# NTC_6_Shoulder.net
KiCad netlist of a schematic drawn in Altium Designer
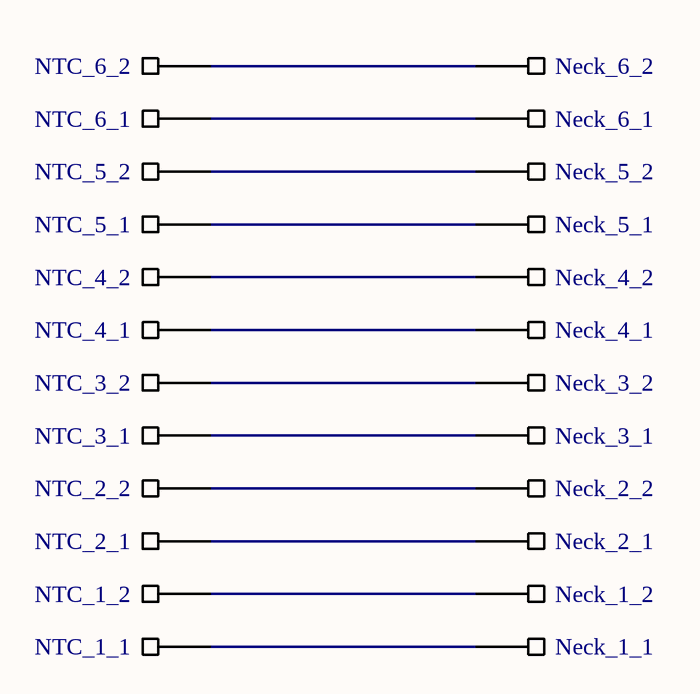
[diagram p0: NTC_6_Shoulder.SchDoc]

(export (version "E")
  (design (tool "Eeschema 10.0.6"))
  (components
    (comp (ref "Neck_1_1")
      (value "Pad")
      (footprint "Generic_Pad_1.5x1.5")
      (description "Pad 1.5mm x 1.5mm")
      (libsource (lib "libNico") (part "Generic_Pad_1.5x1.5"))
    )
    (comp (ref "Neck_1_2")
      (value "Pad")
      (footprint "Generic_Pad_1.5x1.5")
      (description "Pad 1.5mm x 1.5mm")
      (libsource (lib "libNico") (part "Generic_Pad_1.5x1.5"))
    )
    (comp (ref "Neck_2_1")
      (value "Pad")
      (footprint "Generic_Pad_1.5x1.5")
      (description "Pad 1.5mm x 1.5mm")
      (libsource (lib "libNico") (part "Generic_Pad_1.5x1.5"))
    )
    (comp (ref "Neck_2_2")
      (value "Pad")
      (footprint "Generic_Pad_1.5x1.5")
      (description "Pad 1.5mm x 1.5mm")
      (libsource (lib "libNico") (part "Generic_Pad_1.5x1.5"))
    )
    (comp (ref "Neck_3_1")
      (value "Pad")
      (footprint "Generic_Pad_1.5x1.5")
      (description "Pad 1.5mm x 1.5mm")
      (libsource (lib "libNico") (part "Generic_Pad_1.5x1.5"))
    )
    (comp (ref "Neck_3_2")
      (value "Pad")
      (footprint "Generic_Pad_1.5x1.5")
      (description "Pad 1.5mm x 1.5mm")
      (libsource (lib "libNico") (part "Generic_Pad_1.5x1.5"))
    )
    (comp (ref "Neck_4_1")
      (value "Pad")
      (footprint "Generic_Pad_1.5x1.5")
      (description "Pad 1.5mm x 1.5mm")
      (libsource (lib "libNico") (part "Generic_Pad_1.5x1.5"))
    )
    (comp (ref "Neck_4_2")
      (value "Pad")
      (footprint "Generic_Pad_1.5x1.5")
      (description "Pad 1.5mm x 1.5mm")
      (libsource (lib "libNico") (part "Generic_Pad_1.5x1.5"))
    )
    (comp (ref "Neck_5_1")
      (value "Pad")
      (footprint "Generic_Pad_1.5x1.5")
      (description "Pad 1.5mm x 1.5mm")
      (libsource (lib "libNico") (part "Generic_Pad_1.5x1.5"))
    )
    (comp (ref "Neck_5_2")
      (value "Pad")
      (footprint "Generic_Pad_1.5x1.5")
      (description "Pad 1.5mm x 1.5mm")
      (libsource (lib "libNico") (part "Generic_Pad_1.5x1.5"))
    )
    (comp (ref "Neck_6_1")
      (value "Pad")
      (footprint "Generic_Pad_1.5x1.5")
      (description "Pad 1.5mm x 1.5mm")
      (libsource (lib "libNico") (part "Generic_Pad_1.5x1.5"))
    )
    (comp (ref "Neck_6_2")
      (value "Pad")
      (footprint "Generic_Pad_1.5x1.5")
      (description "Pad 1.5mm x 1.5mm")
      (libsource (lib "libNico") (part "Generic_Pad_1.5x1.5"))
    )
    (comp (ref "NTC_1_1")
      (value "Pad")
      (footprint "Generic_Pad_1.5x1.5")
      (description "Pad 1.5mm x 1.5mm")
      (libsource (lib "libNico") (part "Generic_Pad_1.5x1.5"))
    )
    (comp (ref "NTC_1_2")
      (value "Pad")
      (footprint "Generic_Pad_1.5x1.5")
      (description "Pad 1.5mm x 1.5mm")
      (libsource (lib "libNico") (part "Generic_Pad_1.5x1.5"))
    )
    (comp (ref "NTC_2_1")
      (value "Pad")
      (footprint "Generic_Pad_1.5x1.5")
      (description "Pad 1.5mm x 1.5mm")
      (libsource (lib "libNico") (part "Generic_Pad_1.5x1.5"))
    )
    (comp (ref "NTC_2_2")
      (value "Pad")
      (footprint "Generic_Pad_1.5x1.5")
      (description "Pad 1.5mm x 1.5mm")
      (libsource (lib "libNico") (part "Generic_Pad_1.5x1.5"))
    )
    (comp (ref "NTC_3_1")
      (value "Pad")
      (footprint "Generic_Pad_1.5x1.5")
      (description "Pad 1.5mm x 1.5mm")
      (libsource (lib "libNico") (part "Generic_Pad_1.5x1.5"))
    )
    (comp (ref "NTC_3_2")
      (value "Pad")
      (footprint "Generic_Pad_1.5x1.5")
      (description "Pad 1.5mm x 1.5mm")
      (libsource (lib "libNico") (part "Generic_Pad_1.5x1.5"))
    )
    (comp (ref "NTC_4_1")
      (value "Pad")
      (footprint "Generic_Pad_1.5x1.5")
      (description "Pad 1.5mm x 1.5mm")
      (libsource (lib "libNico") (part "Generic_Pad_1.5x1.5"))
    )
    (comp (ref "NTC_4_2")
      (value "Pad")
      (footprint "Generic_Pad_1.5x1.5")
      (description "Pad 1.5mm x 1.5mm")
      (libsource (lib "libNico") (part "Generic_Pad_1.5x1.5"))
    )
    (comp (ref "NTC_5_1")
      (value "Pad")
      (footprint "Generic_Pad_1.5x1.5")
      (description "Pad 1.5mm x 1.5mm")
      (libsource (lib "libNico") (part "Generic_Pad_1.5x1.5"))
    )
    (comp (ref "NTC_5_2")
      (value "Pad")
      (footprint "Generic_Pad_1.5x1.5")
      (description "Pad 1.5mm x 1.5mm")
      (libsource (lib "libNico") (part "Generic_Pad_1.5x1.5"))
    )
    (comp (ref "NTC_6_1")
      (value "Pad")
      (footprint "Generic_Pad_1.5x1.5")
      (description "Pad 1.5mm x 1.5mm")
      (libsource (lib "libNico") (part "Generic_Pad_1.5x1.5"))
    )
    (comp (ref "NTC_6_2")
      (value "Pad")
      (footprint "Generic_Pad_1.5x1.5")
      (description "Pad 1.5mm x 1.5mm")
      (libsource (lib "libNico") (part "Generic_Pad_1.5x1.5"))
    )
  )
  (nets
    (net (code "1") (name "Net-(NTC_1_1-Pad)") (class "Default")
      (node (ref "NTC_1_1") (pin "P") (pinfunction "Pad_P") (pintype "passive"))
      (node (ref "Neck_1_1") (pin "P") (pinfunction "Pad_P") (pintype "passive"))
    )
    (net (code "2") (name "Net-(NTC_1_2-Pad)") (class "Default")
      (node (ref "NTC_1_2") (pin "P") (pinfunction "Pad_P") (pintype "passive"))
      (node (ref "Neck_1_2") (pin "P") (pinfunction "Pad_P") (pintype "passive"))
    )
    (net (code "3") (name "Net-(NTC_2_1-Pad)") (class "Default")
      (node (ref "NTC_2_1") (pin "P") (pinfunction "Pad_P") (pintype "passive"))
      (node (ref "Neck_2_1") (pin "P") (pinfunction "Pad_P") (pintype "passive"))
    )
    (net (code "4") (name "Net-(NTC_2_2-Pad)") (class "Default")
      (node (ref "NTC_2_2") (pin "P") (pinfunction "Pad_P") (pintype "passive"))
      (node (ref "Neck_2_2") (pin "P") (pinfunction "Pad_P") (pintype "passive"))
    )
    (net (code "5") (name "Net-(NTC_3_1-Pad)") (class "Default")
      (node (ref "NTC_3_1") (pin "P") (pinfunction "Pad_P") (pintype "passive"))
      (node (ref "Neck_3_1") (pin "P") (pinfunction "Pad_P") (pintype "passive"))
    )
    (net (code "6") (name "Net-(NTC_3_2-Pad)") (class "Default")
      (node (ref "NTC_3_2") (pin "P") (pinfunction "Pad_P") (pintype "passive"))
      (node (ref "Neck_3_2") (pin "P") (pinfunction "Pad_P") (pintype "passive"))
    )
    (net (code "7") (name "Net-(NTC_4_1-Pad)") (class "Default")
      (node (ref "NTC_4_1") (pin "P") (pinfunction "Pad_P") (pintype "passive"))
      (node (ref "Neck_4_1") (pin "P") (pinfunction "Pad_P") (pintype "passive"))
    )
    (net (code "8") (name "Net-(NTC_4_2-Pad)") (class "Default")
      (node (ref "NTC_4_2") (pin "P") (pinfunction "Pad_P") (pintype "passive"))
      (node (ref "Neck_4_2") (pin "P") (pinfunction "Pad_P") (pintype "passive"))
    )
    (net (code "9") (name "Net-(NTC_5_1-Pad)") (class "Default")
      (node (ref "NTC_5_1") (pin "P") (pinfunction "Pad_P") (pintype "passive"))
      (node (ref "Neck_5_1") (pin "P") (pinfunction "Pad_P") (pintype "passive"))
    )
    (net (code "10") (name "Net-(NTC_5_2-Pad)") (class "Default")
      (node (ref "NTC_5_2") (pin "P") (pinfunction "Pad_P") (pintype "passive"))
      (node (ref "Neck_5_2") (pin "P") (pinfunction "Pad_P") (pintype "passive"))
    )
    (net (code "11") (name "Net-(NTC_6_1-Pad)") (class "Default")
      (node (ref "NTC_6_1") (pin "P") (pinfunction "Pad_P") (pintype "passive"))
      (node (ref "Neck_6_1") (pin "P") (pinfunction "Pad_P") (pintype "passive"))
    )
    (net (code "12") (name "Net-(NTC_6_2-Pad)") (class "Default")
      (node (ref "NTC_6_2") (pin "P") (pinfunction "Pad_P") (pintype "passive"))
      (node (ref "Neck_6_2") (pin "P") (pinfunction "Pad_P") (pintype "passive"))
    )
  )
)
